# prisvit.net
KiCad netlist of a schematic drawn in EAGLE
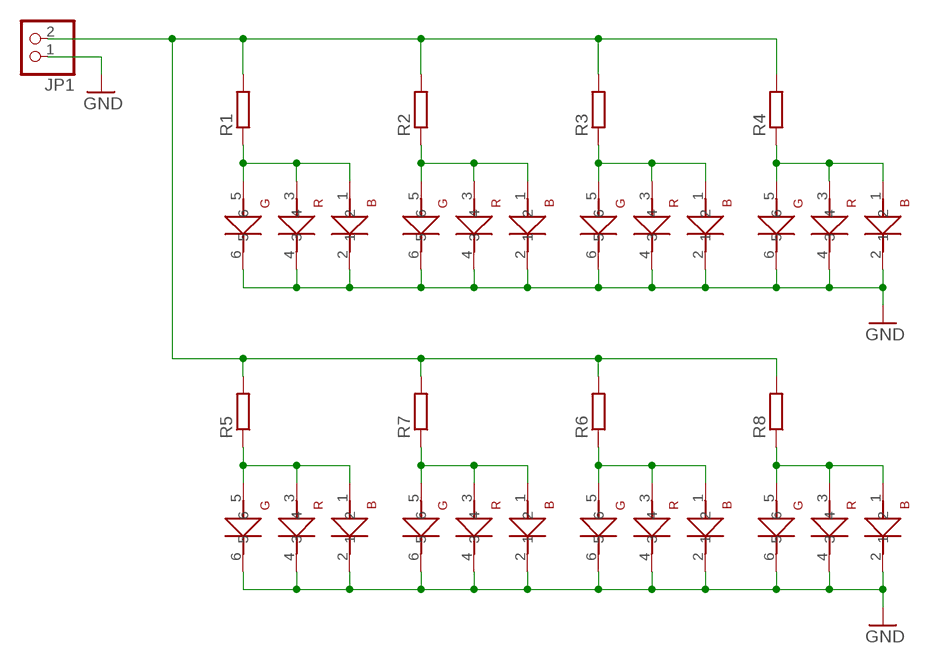
[diagram p0: schematic, sheet 1]

(export (version "E")
  (design (tool "Eeschema 10.0.6"))
  (components
    (comp (ref "JP1")
      (value "PINHD-1X2")
      (footprint "eagle-import:1X02")
      (libsource (lib "eagle-import") (part "PINHD-1X2"))
    )
    (comp (ref "R1")
      (value "R-EU_M2012")
      (footprint "eagle-import:M2012")
      (libsource (lib "eagle-import") (part "R-EU_M2012"))
    )
    (comp (ref "R2")
      (value "R-EU_M2012")
      (footprint "eagle-import:M2012")
      (libsource (lib "eagle-import") (part "R-EU_M2012"))
    )
    (comp (ref "R3")
      (value "R-EU_M2012")
      (footprint "eagle-import:M2012")
      (libsource (lib "eagle-import") (part "R-EU_M2012"))
    )
    (comp (ref "R4")
      (value "R-EU_M2012")
      (footprint "eagle-import:M2012")
      (libsource (lib "eagle-import") (part "R-EU_M2012"))
    )
    (comp (ref "R5")
      (value "R-EU_M2012")
      (footprint "eagle-import:M2012")
      (libsource (lib "eagle-import") (part "R-EU_M2012"))
    )
    (comp (ref "R6")
      (value "R-EU_M2012")
      (footprint "eagle-import:M2012")
      (libsource (lib "eagle-import") (part "R-EU_M2012"))
    )
    (comp (ref "R7")
      (value "R-EU_M2012")
      (footprint "eagle-import:M2012")
      (libsource (lib "eagle-import") (part "R-EU_M2012"))
    )
    (comp (ref "R8")
      (value "R-EU_M2012")
      (footprint "eagle-import:M2012")
      (libsource (lib "eagle-import") (part "R-EU_M2012"))
    )
    (comp (ref "U$1")
      (value "5050_LED")
      (footprint "eagle-import:5050_LED")
      (libsource (lib "eagle-import") (part "5050_LED"))
    )
    (comp (ref "U$2")
      (value "5050_LED")
      (footprint "eagle-import:5050_LED")
      (libsource (lib "eagle-import") (part "5050_LED"))
    )
    (comp (ref "U$3")
      (value "5050_LED")
      (footprint "eagle-import:5050_LED")
      (libsource (lib "eagle-import") (part "5050_LED"))
    )
    (comp (ref "U$4")
      (value "5050_LED")
      (footprint "eagle-import:5050_LED")
      (libsource (lib "eagle-import") (part "5050_LED"))
    )
    (comp (ref "U$5")
      (value "5050_LED")
      (footprint "eagle-import:5050_LED")
      (libsource (lib "eagle-import") (part "5050_LED"))
    )
    (comp (ref "U$6")
      (value "5050_LED")
      (footprint "eagle-import:5050_LED")
      (libsource (lib "eagle-import") (part "5050_LED"))
    )
    (comp (ref "U$7")
      (value "5050_LED")
      (footprint "eagle-import:5050_LED")
      (libsource (lib "eagle-import") (part "5050_LED"))
    )
    (comp (ref "U$8")
      (value "5050_LED")
      (footprint "eagle-import:5050_LED")
      (libsource (lib "eagle-import") (part "5050_LED"))
    )
  )
  (nets
    (net (code "1") (name "GND") (class "Default")
      (node (ref "JP1") (pin "1") (pinfunction "1_1") (pintype "passive"))
      (node (ref "U$1") (pin "2") (pinfunction "2_2") (pintype "bidirectional"))
      (node (ref "U$1") (pin "4") (pinfunction "4_4") (pintype "bidirectional"))
      (node (ref "U$1") (pin "6") (pinfunction "6_6") (pintype "bidirectional"))
      (node (ref "U$2") (pin "2") (pinfunction "2_2") (pintype "bidirectional"))
      (node (ref "U$2") (pin "4") (pinfunction "4_4") (pintype "bidirectional"))
      (node (ref "U$2") (pin "6") (pinfunction "6_6") (pintype "bidirectional"))
      (node (ref "U$3") (pin "2") (pinfunction "2_2") (pintype "bidirectional"))
      (node (ref "U$3") (pin "4") (pinfunction "4_4") (pintype "bidirectional"))
      (node (ref "U$3") (pin "6") (pinfunction "6_6") (pintype "bidirectional"))
      (node (ref "U$4") (pin "2") (pinfunction "2_2") (pintype "bidirectional"))
      (node (ref "U$4") (pin "4") (pinfunction "4_4") (pintype "bidirectional"))
      (node (ref "U$4") (pin "6") (pinfunction "6_6") (pintype "bidirectional"))
      (node (ref "U$5") (pin "2") (pinfunction "2_2") (pintype "bidirectional"))
      (node (ref "U$5") (pin "4") (pinfunction "4_4") (pintype "bidirectional"))
      (node (ref "U$5") (pin "6") (pinfunction "6_6") (pintype "bidirectional"))
      (node (ref "U$6") (pin "2") (pinfunction "2_2") (pintype "bidirectional"))
      (node (ref "U$6") (pin "4") (pinfunction "4_4") (pintype "bidirectional"))
      (node (ref "U$6") (pin "6") (pinfunction "6_6") (pintype "bidirectional"))
      (node (ref "U$7") (pin "2") (pinfunction "2_2") (pintype "bidirectional"))
      (node (ref "U$7") (pin "4") (pinfunction "4_4") (pintype "bidirectional"))
      (node (ref "U$7") (pin "6") (pinfunction "6_6") (pintype "bidirectional"))
      (node (ref "U$8") (pin "2") (pinfunction "2_2") (pintype "bidirectional"))
      (node (ref "U$8") (pin "4") (pinfunction "4_4") (pintype "bidirectional"))
      (node (ref "U$8") (pin "6") (pinfunction "6_6") (pintype "bidirectional"))
    )
    (net (code "2") (name "Net-(JP1-Pad2)") (class "Default")
      (node (ref "JP1") (pin "2") (pinfunction "2_2") (pintype "passive"))
      (node (ref "R1") (pin "2") (pinfunction "2_2") (pintype "passive"))
      (node (ref "R2") (pin "2") (pinfunction "2_2") (pintype "passive"))
      (node (ref "R3") (pin "2") (pinfunction "2_2") (pintype "passive"))
      (node (ref "R4") (pin "2") (pinfunction "2_2") (pintype "passive"))
      (node (ref "R5") (pin "2") (pinfunction "2_2") (pintype "passive"))
      (node (ref "R6") (pin "2") (pinfunction "2_2") (pintype "passive"))
      (node (ref "R7") (pin "2") (pinfunction "2_2") (pintype "passive"))
      (node (ref "R8") (pin "2") (pinfunction "2_2") (pintype "passive"))
    )
    (net (code "3") (name "Net-(R1-Pad1)") (class "Default")
      (node (ref "R1") (pin "1") (pinfunction "1_1") (pintype "passive"))
      (node (ref "U$2") (pin "1") (pinfunction "1_1") (pintype "bidirectional"))
      (node (ref "U$2") (pin "3") (pinfunction "3_3") (pintype "bidirectional"))
      (node (ref "U$2") (pin "5") (pinfunction "5_5") (pintype "bidirectional"))
    )
    (net (code "4") (name "Net-(R2-Pad1)") (class "Default")
      (node (ref "R2") (pin "1") (pinfunction "1_1") (pintype "passive"))
      (node (ref "U$3") (pin "1") (pinfunction "1_1") (pintype "bidirectional"))
      (node (ref "U$3") (pin "3") (pinfunction "3_3") (pintype "bidirectional"))
      (node (ref "U$3") (pin "5") (pinfunction "5_5") (pintype "bidirectional"))
    )
    (net (code "5") (name "Net-(R3-Pad1)") (class "Default")
      (node (ref "R3") (pin "1") (pinfunction "1_1") (pintype "passive"))
      (node (ref "U$4") (pin "1") (pinfunction "1_1") (pintype "bidirectional"))
      (node (ref "U$4") (pin "3") (pinfunction "3_3") (pintype "bidirectional"))
      (node (ref "U$4") (pin "5") (pinfunction "5_5") (pintype "bidirectional"))
    )
    (net (code "6") (name "Net-(R4-Pad1)") (class "Default")
      (node (ref "R4") (pin "1") (pinfunction "1_1") (pintype "passive"))
      (node (ref "U$6") (pin "1") (pinfunction "1_1") (pintype "bidirectional"))
      (node (ref "U$6") (pin "3") (pinfunction "3_3") (pintype "bidirectional"))
      (node (ref "U$6") (pin "5") (pinfunction "5_5") (pintype "bidirectional"))
    )
    (net (code "7") (name "Net-(R5-Pad1)") (class "Default")
      (node (ref "R5") (pin "1") (pinfunction "1_1") (pintype "passive"))
      (node (ref "U$8") (pin "1") (pinfunction "1_1") (pintype "bidirectional"))
      (node (ref "U$8") (pin "3") (pinfunction "3_3") (pintype "bidirectional"))
      (node (ref "U$8") (pin "5") (pinfunction "5_5") (pintype "bidirectional"))
    )
    (net (code "8") (name "Net-(R6-Pad1)") (class "Default")
      (node (ref "R6") (pin "1") (pinfunction "1_1") (pintype "passive"))
      (node (ref "U$5") (pin "1") (pinfunction "1_1") (pintype "bidirectional"))
      (node (ref "U$5") (pin "3") (pinfunction "3_3") (pintype "bidirectional"))
      (node (ref "U$5") (pin "5") (pinfunction "5_5") (pintype "bidirectional"))
    )
    (net (code "9") (name "Net-(R7-Pad1)") (class "Default")
      (node (ref "R7") (pin "1") (pinfunction "1_1") (pintype "passive"))
      (node (ref "U$1") (pin "1") (pinfunction "1_1") (pintype "bidirectional"))
      (node (ref "U$1") (pin "3") (pinfunction "3_3") (pintype "bidirectional"))
      (node (ref "U$1") (pin "5") (pinfunction "5_5") (pintype "bidirectional"))
    )
    (net (code "10") (name "Net-(R8-Pad1)") (class "Default")
      (node (ref "R8") (pin "1") (pinfunction "1_1") (pintype "passive"))
      (node (ref "U$7") (pin "1") (pinfunction "1_1") (pintype "bidirectional"))
      (node (ref "U$7") (pin "3") (pinfunction "3_3") (pintype "bidirectional"))
      (node (ref "U$7") (pin "5") (pinfunction "5_5") (pintype "bidirectional"))
    )
  )
)
